# ADCS_C2Sv0_1_-_Shield_TopLevel.net
KiCad netlist of a schematic drawn in Altium Designer
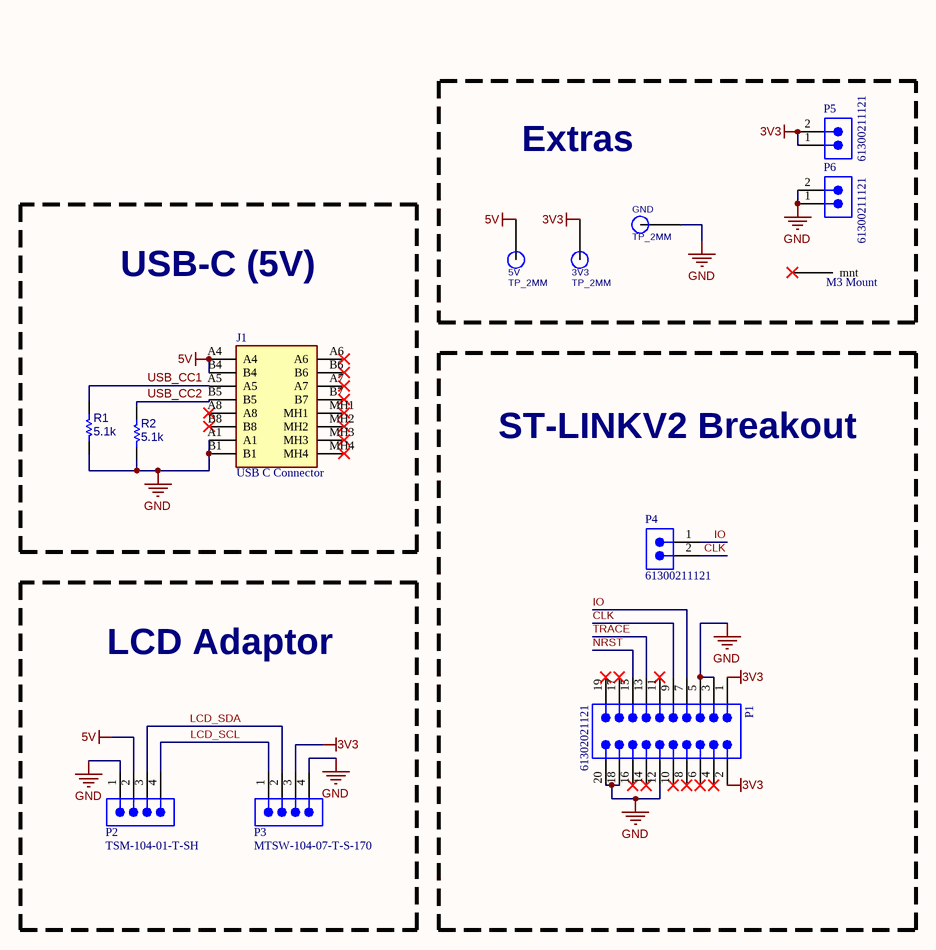
[diagram p0: ADCS C2Sv0.1 - Shield_TopLevel.SchDoc]

(export (version "E")
  (design (tool "Eeschema 10.0.6"))
  (components
    (comp (ref "3V3") (value "TP_2MM") (footprint "TESTPOINT 2MM") (libsource (lib "C2S") (part "TP_2MM")))
    (comp (ref "5V") (value "TP_2MM") (footprint "TESTPOINT 2MM") (libsource (lib "C2S") (part "TP_2MM")))
    (comp (ref "GND") (value "TP_2MM") (footprint "TESTPOINT 2MM") (libsource (lib "C2S") (part "TP_2MM")))
    (comp (ref "J1")
      (value "USB C Connector")
      (footprint "UJ20CHGMSMT2P16TR")
      (description "UJ20-C-H-G-MSMT-2-P16-TR Connector")
      (fields
        (field (name "MOUSER PART NUMBER") "179-UJ20CHGMSMT2P16T")
        (field (name "MANUFACTURER_PART_NUMBER") "UJ20-C-H-G-MSMT-2-P16-TR")
        (field (name "AUTHOR") "Raphael Ho")
      )
      (libsource (lib "Perth Aerospace Student Team") (part "UJ20-C-H-G-MSMT-2-P16-TR"))
    )
    (comp (ref "MNT1")
      (value "M3 Mount")
      (footprint "M3_Mount-Footprint-1")
      (description "M3 mounting hole")
      (fields (field (name "AUTHOR") "Raphael Ho"))
      (libsource (lib "Perth Aerospace Student Team") (part "M3_Mount-Symbol-1"))
    )
    (comp (ref "P1")
      (value "61302021121")
      (footprint "61302021121")
      (description "THT Vertical Pin Header WR-PHD, Pitch 2.54 mm, Dual Row, 20 pins")
      (libsource (lib "Altium Content Vault") (part "Header_Male_2R_20P"))
    )
    (comp (ref "P2")
      (value "TSM-104-01-T-SH")
      (footprint "SMTC-TSM-104-01-X-SH")
      (fields (field (name "MANUFACTURER") "Samtec"))
      (libsource (lib "Altium Content Vault") (part "SMTC-TSM-104-01-X-SH"))
    )
    (comp (ref "P3")
      (value "MTSW-104-07-T-S-170")
      (footprint "SMTC-MTSW-104-07-X-S-170")
      (fields (field (name "MANUFACTURER") "Samtec"))
      (libsource (lib "Altium Content Vault") (part "SMTC-MTSW-104-07-X-S-170"))
    )
    (comp (ref "P4")
      (value "61300211121")
      (footprint "61300211121")
      (description "WR-PHD Pin Header, THT, Vertical, pitch 2.54mm, 1 Row, 2P")
      (fields (field (name "MANUFACTURER") "Wurth Elektronik"))
      (libsource (lib "Perth Aerospace Student Team") (part "62000211121"))
    )
    (comp (ref "P5")
      (value "61300211121")
      (footprint "61300211121")
      (description "WR-PHD Pin Header, THT, Vertical, pitch 2.54mm, 1 Row, 2P")
      (fields (field (name "MANUFACTURER") "Wurth Elektronik"))
      (libsource (lib "Perth Aerospace Student Team") (part "62000211121"))
    )
    (comp (ref "P6")
      (value "61300211121")
      (footprint "61300211121")
      (description "WR-PHD Pin Header, THT, Vertical, pitch 2.54mm, 1 Row, 2P")
      (fields (field (name "MANUFACTURER") "Wurth Elektronik"))
      (libsource (lib "Perth Aerospace Student Team") (part "62000211121"))
    )
    (comp (ref "R1")
      (value "5.1k")
      (footprint "RESC1608X55X25ML10T15-1")
      (description "Chip Resistor, 10k Ohm, 0.1 W, -55 to 155 degC, 0603 (1608 Metric)")
      (fields
        (field (name "POWER") "100mW")
        (field (name "TOLERANCE") "1%")
        (field (name "CREATED BY") "Micah Randall")
      )
      (libsource (lib "Perth Aerospace Student Team") (part "CMP-009-00006-5"))
    )
    (comp (ref "R2")
      (value "5.1k")
      (footprint "RESC1608X55X25ML10T15-1")
      (description "Chip Resistor, 10k Ohm, 0.1 W, -55 to 155 degC, 0603 (1608 Metric)")
      (fields
        (field (name "POWER") "100mW")
        (field (name "TOLERANCE") "1%")
        (field (name "CREATED BY") "Micah Randall")
      )
      (libsource (lib "Perth Aerospace Student Team") (part "CMP-009-00006-5"))
    )
  )
  (nets
    (net (code "1") (name "/CLK") (class "Default")
      (node (ref "P1") (pin "9") (pinfunction "9_9") (pintype "passive"))
      (node (ref "P4") (pin "2") (pinfunction "2_2") (pintype "passive"))
    )
    (net (code "2") (name "/IO") (class "Default")
      (node (ref "P1") (pin "7") (pinfunction "7_7") (pintype "passive"))
      (node (ref "P4") (pin "1") (pinfunction "1_1") (pintype "passive"))
    )
    (net (code "3") (name "/LCD_SCL") (class "Default")
      (node (ref "P2") (pin "4") (pinfunction "4_4") (pintype "passive"))
      (node (ref "P3") (pin "1") (pinfunction "1_1") (pintype "passive"))
    )
    (net (code "4") (name "/LCD_SDA") (class "Default")
      (node (ref "P2") (pin "3") (pinfunction "3_3") (pintype "passive"))
      (node (ref "P3") (pin "2") (pinfunction "2_2") (pintype "passive"))
    )
    (net (code "5") (name "/NRST") (class "Default")
      (node (ref "P1") (pin "15") (pinfunction "15_15") (pintype "passive"))
    )
    (net (code "6") (name "/TRACE") (class "Default")
      (node (ref "P1") (pin "13") (pinfunction "13_13") (pintype "passive"))
    )
    (net (code "7") (name "/USB_CC1") (class "Default")
      (node (ref "J1") (pin "A5") (pinfunction "A5_A5") (pintype "passive"))
      (node (ref "R1") (pin "1") (pinfunction "1_1") (pintype "passive"))
    )
    (net (code "8") (name "/USB_CC2") (class "Default")
      (node (ref "J1") (pin "B5") (pinfunction "B5_B5") (pintype "passive"))
      (node (ref "R2") (pin "1") (pinfunction "1_1") (pintype "passive"))
    )
    (net (code "9") (name "3V3") (class "Default")
      (node (ref "3V3") (pin "TP") (pinfunction "TP_2MM_TP") (pintype "passive"))
      (node (ref "P1") (pin "1") (pinfunction "1_1") (pintype "passive"))
      (node (ref "P1") (pin "2") (pinfunction "2_2") (pintype "passive"))
      (node (ref "P3") (pin "3") (pinfunction "3_3") (pintype "passive"))
      (node (ref "P5") (pin "1") (pinfunction "1_1") (pintype "passive"))
      (node (ref "P5") (pin "2") (pinfunction "2_2") (pintype "passive"))
    )
    (net (code "10") (name "5V") (class "Default")
      (node (ref "5V") (pin "TP") (pinfunction "TP_2MM_TP") (pintype "passive"))
      (node (ref "J1") (pin "A4") (pinfunction "A4_A4") (pintype "passive"))
      (node (ref "J1") (pin "B4") (pinfunction "B4_B4") (pintype "passive"))
      (node (ref "P2") (pin "2") (pinfunction "2_2") (pintype "passive"))
    )
    (net (code "11") (name "GND") (class "Default")
      (node (ref "GND") (pin "TP") (pinfunction "TP_2MM_TP") (pintype "passive"))
      (node (ref "J1") (pin "A1") (pinfunction "A1_A1") (pintype "passive"))
      (node (ref "J1") (pin "B1") (pinfunction "B1_B1") (pintype "passive"))
      (node (ref "P1") (pin "12") (pinfunction "12_12") (pintype "passive"))
      (node (ref "P1") (pin "18") (pinfunction "18_18") (pintype "passive"))
      (node (ref "P1") (pin "20") (pinfunction "20_20") (pintype "passive"))
      (node (ref "P1") (pin "3") (pinfunction "3_3") (pintype "passive"))
      (node (ref "P1") (pin "5") (pinfunction "5_5") (pintype "passive"))
      (node (ref "P2") (pin "1") (pinfunction "1_1") (pintype "passive"))
      (node (ref "P3") (pin "4") (pinfunction "4_4") (pintype "passive"))
      (node (ref "P6") (pin "1") (pinfunction "1_1") (pintype "passive"))
      (node (ref "P6") (pin "2") (pinfunction "2_2") (pintype "passive"))
      (node (ref "R1") (pin "2") (pinfunction "2_2") (pintype "passive"))
      (node (ref "R2") (pin "2") (pinfunction "2_2") (pintype "passive"))
    )
    (net (code "12") (name "unconnected-(J1-PadA6)") (class "Default")
      (node (ref "J1") (pin "A6") (pinfunction "A6_A6") (pintype "passive+no_connect"))
    )
    (net (code "13") (name "unconnected-(J1-PadA7)") (class "Default")
      (node (ref "J1") (pin "A7") (pinfunction "A7_A7") (pintype "passive+no_connect"))
    )
    (net (code "14") (name "unconnected-(J1-PadA8)") (class "Default")
      (node (ref "J1") (pin "A8") (pinfunction "A8_A8") (pintype "passive+no_connect"))
    )
    (net (code "15") (name "unconnected-(J1-PadB6)") (class "Default")
      (node (ref "J1") (pin "B6") (pinfunction "B6_B6") (pintype "passive+no_connect"))
    )
    (net (code "16") (name "unconnected-(J1-PadB7)") (class "Default")
      (node (ref "J1") (pin "B7") (pinfunction "B7_B7") (pintype "passive+no_connect"))
    )
    (net (code "17") (name "unconnected-(J1-PadB8)") (class "Default")
      (node (ref "J1") (pin "B8") (pinfunction "B8_B8") (pintype "passive+no_connect"))
    )
    (net (code "18") (name "unconnected-(J1-PadMH1)") (class "Default")
      (node (ref "J1") (pin "MH1") (pinfunction "MH1_MH1") (pintype "passive+no_connect"))
    )
    (net (code "19") (name "unconnected-(J1-PadMH2)") (class "Default")
      (node (ref "J1") (pin "MH2") (pinfunction "MH2_MH2") (pintype "passive+no_connect"))
    )
    (net (code "20") (name "unconnected-(J1-PadMH3)") (class "Default")
      (node (ref "J1") (pin "MH3") (pinfunction "MH3_MH3") (pintype "passive+no_connect"))
    )
    (net (code "21") (name "unconnected-(J1-PadMH4)") (class "Default")
      (node (ref "J1") (pin "MH4") (pinfunction "MH4_MH4") (pintype "passive+no_connect"))
    )
    (net (code "22") (name "unconnected-(MNT1-mnt-Pad1)") (class "Default")
      (node (ref "MNT1") (pin "1") (pinfunction "mnt_1") (pintype "passive+no_connect"))
    )
    (net (code "23") (name "unconnected-(P1-Pad4)") (class "Default")
      (node (ref "P1") (pin "4") (pinfunction "4_4") (pintype "passive+no_connect"))
    )
    (net (code "24") (name "unconnected-(P1-Pad6)") (class "Default")
      (node (ref "P1") (pin "6") (pinfunction "6_6") (pintype "passive+no_connect"))
    )
    (net (code "25") (name "unconnected-(P1-Pad8)") (class "Default")
      (node (ref "P1") (pin "8") (pinfunction "8_8") (pintype "passive+no_connect"))
    )
    (net (code "26") (name "unconnected-(P1-Pad10)") (class "Default")
      (node (ref "P1") (pin "10") (pinfunction "10_10") (pintype "passive+no_connect"))
    )
    (net (code "27") (name "unconnected-(P1-Pad11)") (class "Default")
      (node (ref "P1") (pin "11") (pinfunction "11_11") (pintype "passive+no_connect"))
    )
    (net (code "28") (name "unconnected-(P1-Pad14)") (class "Default")
      (node (ref "P1") (pin "14") (pinfunction "14_14") (pintype "passive+no_connect"))
    )
    (net (code "29") (name "unconnected-(P1-Pad16)") (class "Default")
      (node (ref "P1") (pin "16") (pinfunction "16_16") (pintype "passive+no_connect"))
    )
    (net (code "30") (name "unconnected-(P1-Pad17)") (class "Default")
      (node (ref "P1") (pin "17") (pinfunction "17_17") (pintype "passive+no_connect"))
    )
    (net (code "31") (name "unconnected-(P1-Pad19)") (class "Default")
      (node (ref "P1") (pin "19") (pinfunction "19_19") (pintype "passive+no_connect"))
    )
  )
)
